# type-k.net
KiCad netlist of a schematic drawn in EAGLE
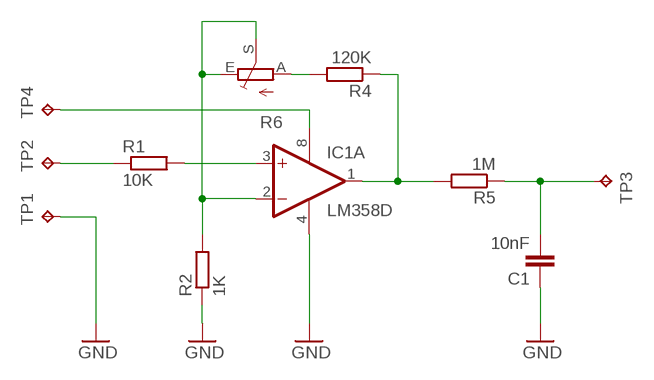
[diagram p0: schematic, sheet 1]

(export (version "E")
  (design (tool "Eeschema 10.0.6"))
  (components
    (comp (ref "C1")
      (value "10nF")
      (footprint "eagle-import:C0805")
      (libsource (lib "eagle-import") (part "C-EUC0805"))
    )
    (comp (ref "IC1")
      (value "LM358D")
      (footprint "eagle-import:SO08")
      (libsource (lib "eagle-import") (part "LM358D"))
    )
    (comp (ref "R1")
      (value "10K")
      (footprint "eagle-import:R0805")
      (libsource (lib "eagle-import") (part "R-EU_R0805"))
    )
    (comp (ref "R2")
      (value "1K")
      (footprint "eagle-import:R0805")
      (libsource (lib "eagle-import") (part "R-EU_R0805"))
    )
    (comp (ref "R4")
      (value "120K")
      (footprint "eagle-import:R0805")
      (libsource (lib "eagle-import") (part "R-EU_R0805"))
    )
    (comp (ref "R5")
      (value "1M")
      (footprint "eagle-import:R0805")
      (libsource (lib "eagle-import") (part "R-EU_R0805"))
    )
    (comp (ref "R6")
      (value "TRIM_EU-CA6V")
      (footprint "eagle-import:CA6V")
      (libsource (lib "eagle-import") (part "TRIM_EU-CA6V"))
    )
    (comp (ref "TP1")
      (value "TPB2,54")
      (footprint "eagle-import:B2,54")
      (libsource (lib "eagle-import") (part "TPB2,54"))
    )
    (comp (ref "TP2")
      (value "TPB2,54")
      (footprint "eagle-import:B2,54")
      (libsource (lib "eagle-import") (part "TPB2,54"))
    )
    (comp (ref "TP3")
      (value "TPB2,54")
      (footprint "eagle-import:B2,54")
      (libsource (lib "eagle-import") (part "TPB2,54"))
    )
    (comp (ref "TP4")
      (value "TPB2,54")
      (footprint "eagle-import:B2,54")
      (libsource (lib "eagle-import") (part "TPB2,54"))
    )
  )
  (nets
    (net (code "1") (name "GND") (class "Default")
      (node (ref "C1") (pin "1") (pinfunction "1_1") (pintype "passive"))
      (node (ref "IC1") (pin "4") (pinfunction "V-_4") (pintype "power_in"))
      (node (ref "R2") (pin "1") (pinfunction "1_1") (pintype "passive"))
      (node (ref "TP1") (pin "TP") (pinfunction "TP_TP") (pintype "input"))
    )
    (net (code "2") (name "Net-(C1-Pad2)") (class "Default")
      (node (ref "C1") (pin "2") (pinfunction "2_2") (pintype "passive"))
      (node (ref "R5") (pin "1") (pinfunction "1_1") (pintype "passive"))
      (node (ref "TP3") (pin "TP") (pinfunction "TP_TP") (pintype "input"))
    )
    (net (code "3") (name "Net-(IC1A-+IN)") (class "Default")
      (node (ref "IC1") (pin "3") (pinfunction "+IN_3") (pintype "input"))
      (node (ref "R1") (pin "2") (pinfunction "2_2") (pintype "passive"))
    )
    (net (code "4") (name "Net-(IC1A--IN)") (class "Default")
      (node (ref "IC1") (pin "2") (pinfunction "-IN_2") (pintype "input"))
      (node (ref "R2") (pin "2") (pinfunction "2_2") (pintype "passive"))
      (node (ref "R6") (pin "E") (pinfunction "E_E") (pintype "passive"))
      (node (ref "R6") (pin "S") (pinfunction "S_S") (pintype "passive"))
    )
    (net (code "5") (name "Net-(IC1A-OUT)") (class "Default")
      (node (ref "IC1") (pin "1") (pinfunction "OUT_1") (pintype "output"))
      (node (ref "R4") (pin "1") (pinfunction "1_1") (pintype "passive"))
      (node (ref "R5") (pin "2") (pinfunction "2_2") (pintype "passive"))
    )
    (net (code "6") (name "Net-(IC1C-V+)") (class "Default")
      (node (ref "IC1") (pin "8") (pinfunction "V+_8") (pintype "power_in"))
      (node (ref "TP4") (pin "TP") (pinfunction "TP_TP") (pintype "input"))
    )
    (net (code "7") (name "Net-(R1-Pad1)") (class "Default")
      (node (ref "R1") (pin "1") (pinfunction "1_1") (pintype "passive"))
      (node (ref "TP2") (pin "TP") (pinfunction "TP_TP") (pintype "input"))
    )
    (net (code "8") (name "Net-(R4-Pad2)") (class "Default")
      (node (ref "R4") (pin "2") (pinfunction "2_2") (pintype "passive"))
      (node (ref "R6") (pin "A") (pinfunction "A_A") (pintype "passive"))
    )
  )
)
